# SCH_USBHub_2025-11-01.net
KiCad netlist of a schematic drawn in EasyEDA
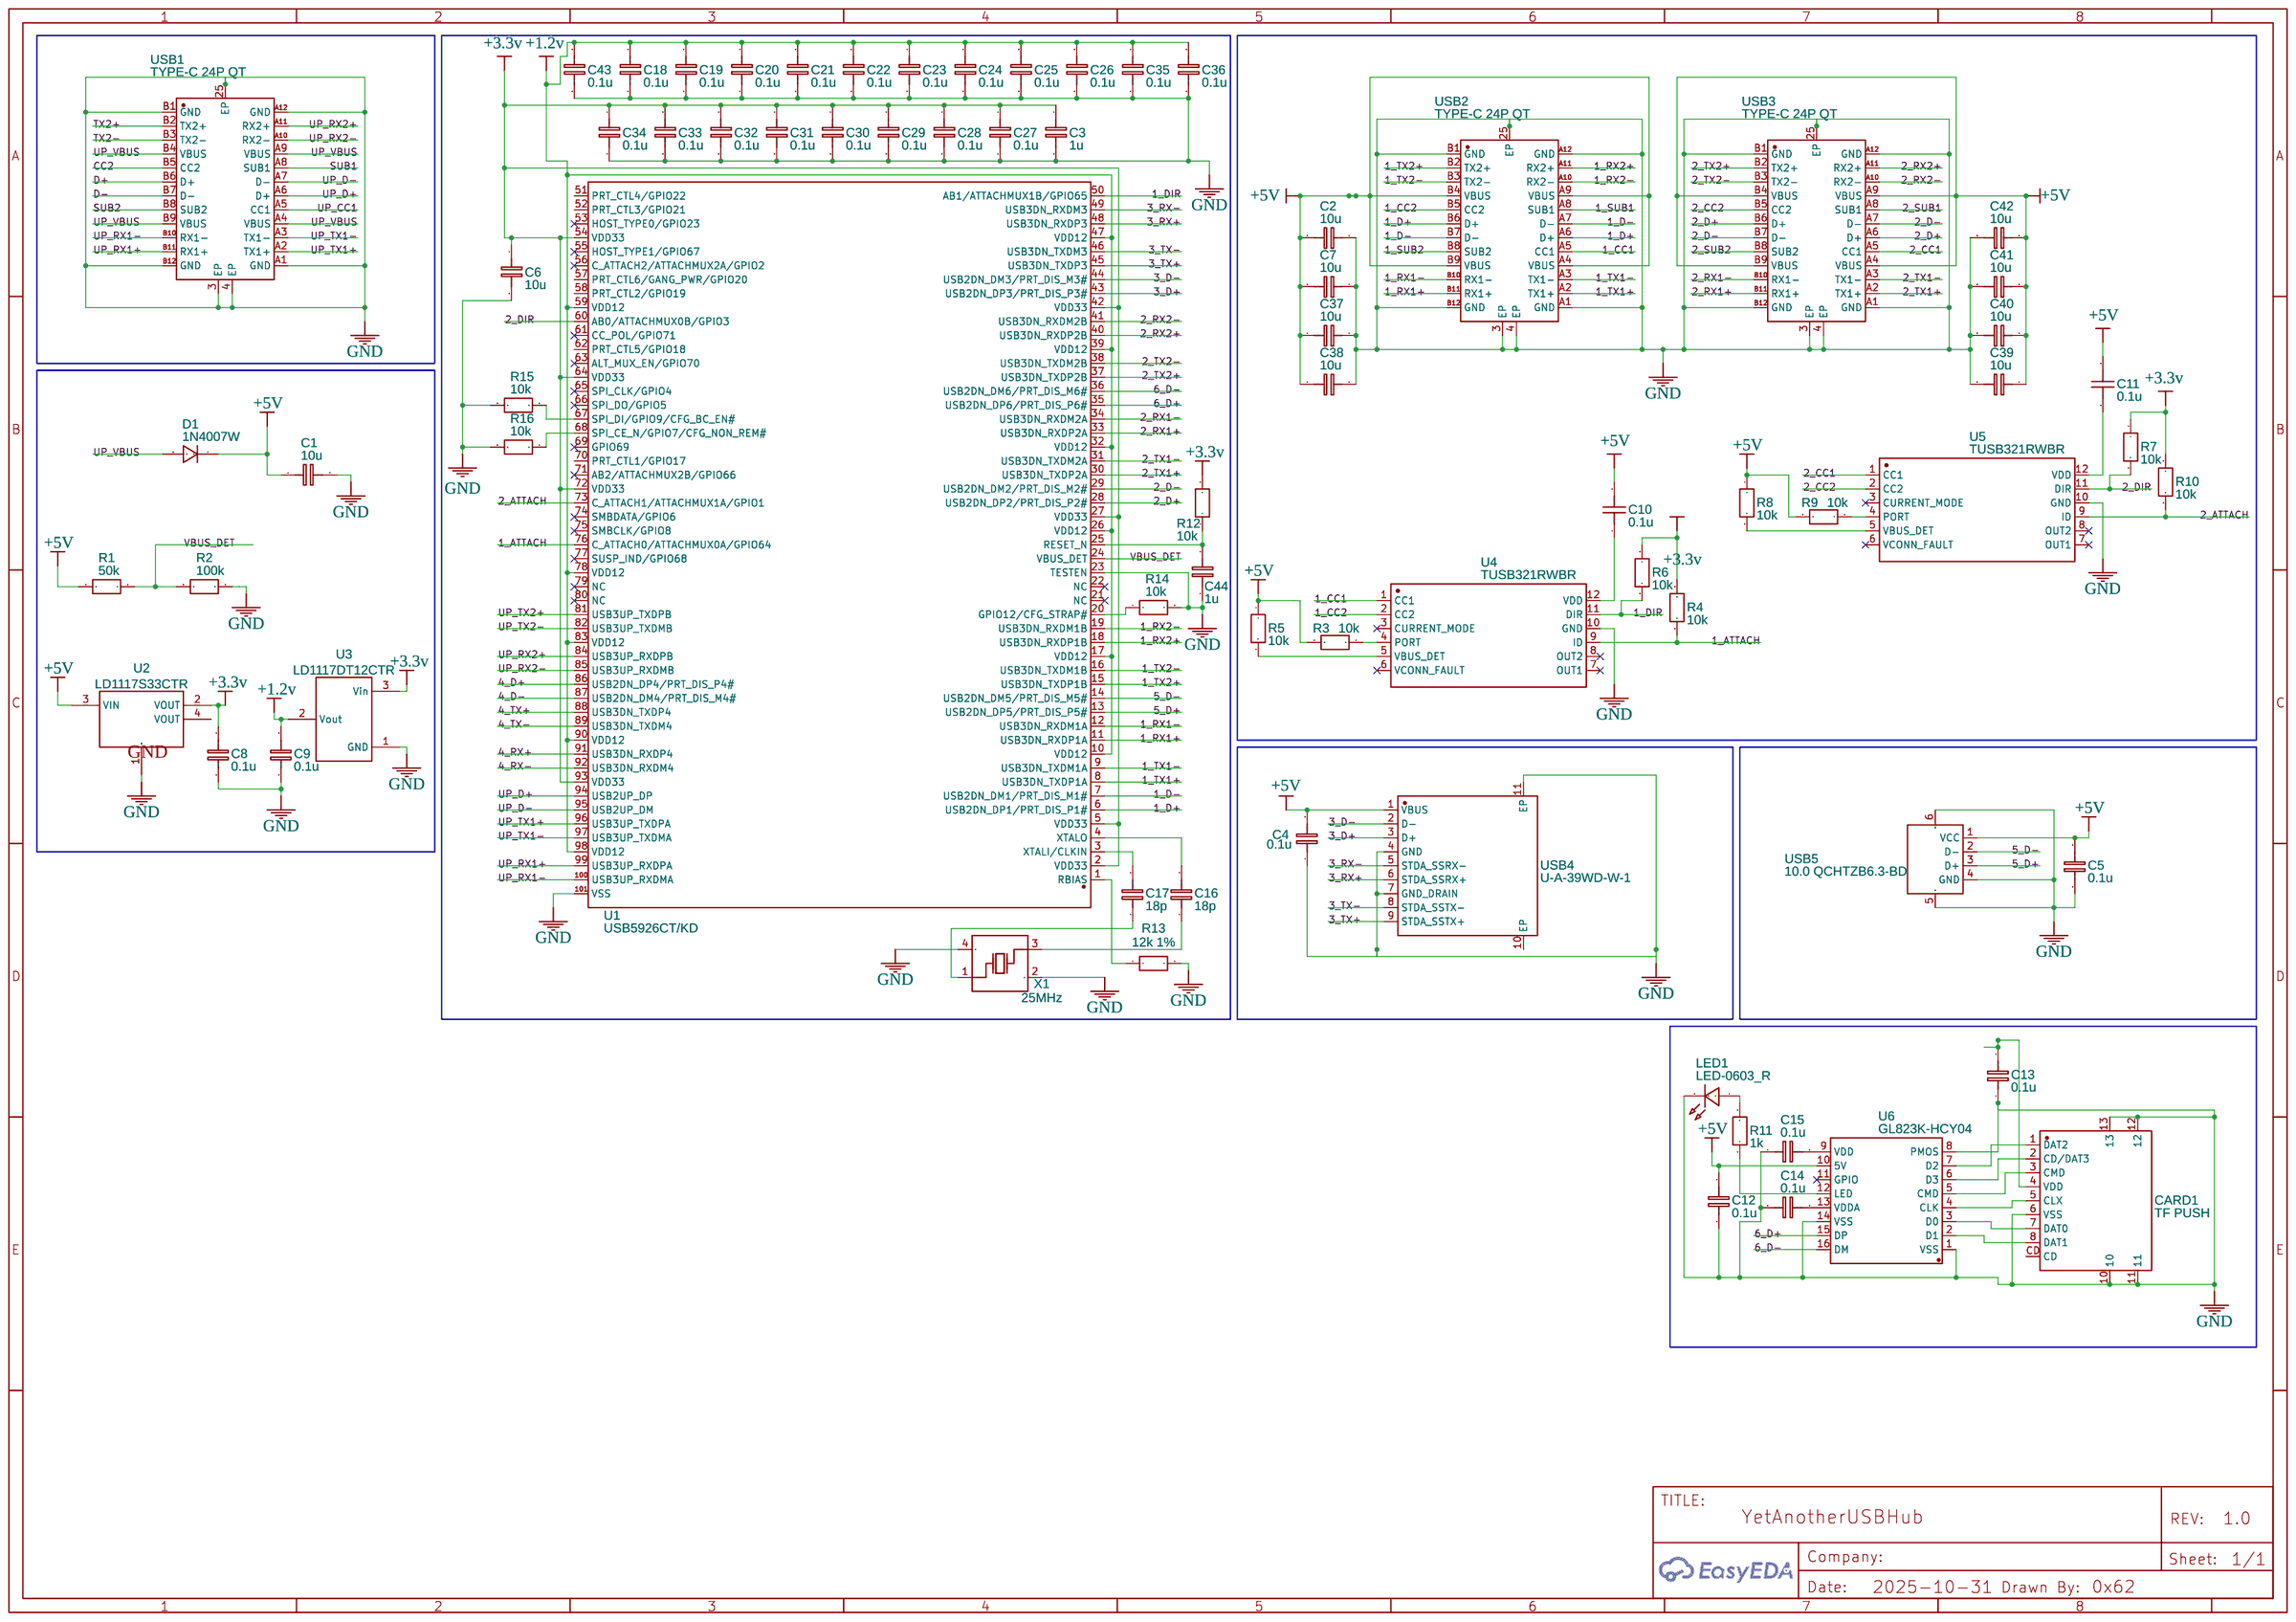
[diagram p0: schematic sheet]

(export (version "E")
  (design (tool "Eeschema 10.0.6"))
  (components
    (comp (ref "C1") (value "10u") (libsource (lib "") (part "C_0603_EU_1")))
    (comp (ref "C2") (value "10u") (libsource (lib "") (part "C_0603_EU_2")))
    (comp (ref "C3") (value "1u") (libsource (lib "") (part "C_0603_EU_7")))
    (comp (ref "C4") (value "0.1u") (libsource (lib "") (part "C_0603_EU")))
    (comp (ref "C5") (value "0.1u") (libsource (lib "") (part "C_0603_EU")))
    (comp (ref "C6") (value "10u") (libsource (lib "") (part "C_0603_EU_6")))
    (comp (ref "C7") (value "10u") (libsource (lib "") (part "C_0603_EU_2")))
    (comp (ref "C8") (value "0.1u") (libsource (lib "") (part "C_0603_EU_4")))
    (comp (ref "C9") (value "0.1u") (libsource (lib "") (part "C_0603_EU_4")))
    (comp (ref "C10") (value "0.1u") (libsource (lib "") (part "C_0603_US_1")))
    (comp (ref "C11") (value "0.1u") (libsource (lib "") (part "C_0603_US")))
    (comp (ref "C12") (value "0.1u") (libsource (lib "") (part "C_0603_EU_3")))
    (comp (ref "C13") (value "0.1u") (libsource (lib "") (part "C_0603_EU_3")))
    (comp (ref "C14") (value "0.1u") (libsource (lib "") (part "C_0603_EU_5")))
    (comp (ref "C15") (value "0.1u") (libsource (lib "") (part "C_0603_EU_5")))
    (comp (ref "C16") (value "18p") (libsource (lib "") (part "C_0603_EU")))
    (comp (ref "C17") (value "18p") (libsource (lib "") (part "C_0603_EU")))
    (comp (ref "C18") (value "0.1u") (libsource (lib "") (part "C_0603_EU_6")))
    (comp (ref "C19") (value "0.1u") (libsource (lib "") (part "C_0603_EU_6")))
    (comp (ref "C20") (value "0.1u") (libsource (lib "") (part "C_0603_EU_7")))
    (comp (ref "C21") (value "0.1u") (libsource (lib "") (part "C_0603_EU_7")))
    (comp (ref "C22") (value "0.1u") (libsource (lib "") (part "C_0603_EU_7")))
    (comp (ref "C23") (value "0.1u") (libsource (lib "") (part "C_0603_EU_7")))
    (comp (ref "C24") (value "0.1u") (libsource (lib "") (part "C_0603_EU_7")))
    (comp (ref "C25") (value "0.1u") (libsource (lib "") (part "C_0603_EU_7")))
    (comp (ref "C26") (value "0.1u") (libsource (lib "") (part "C_0603_EU_7")))
    (comp (ref "C27") (value "0.1u") (libsource (lib "") (part "C_0603_EU_7")))
    (comp (ref "C28") (value "0.1u") (libsource (lib "") (part "C_0603_EU_7")))
    (comp (ref "C29") (value "0.1u") (libsource (lib "") (part "C_0603_EU_7")))
    (comp (ref "C30") (value "0.1u") (libsource (lib "") (part "C_0603_EU_7")))
    (comp (ref "C31") (value "0.1u") (libsource (lib "") (part "C_0603_EU_7")))
    (comp (ref "C32") (value "0.1u") (libsource (lib "") (part "C_0603_EU_6")))
    (comp (ref "C33") (value "0.1u") (libsource (lib "") (part "C_0603_EU_6")))
    (comp (ref "C34") (value "0.1u") (libsource (lib "") (part "C_0603_EU_6")))
    (comp (ref "C35") (value "0.1u") (libsource (lib "") (part "C_0603_EU_7")))
    (comp (ref "C36") (value "0.1u") (libsource (lib "") (part "C_0603_EU_7")))
    (comp (ref "C37") (value "10u") (libsource (lib "") (part "C_0603_EU_2")))
    (comp (ref "C38") (value "10u") (libsource (lib "") (part "C_0603_EU_2")))
    (comp (ref "C39") (value "10u") (libsource (lib "") (part "C_0603_EU_2")))
    (comp (ref "C40") (value "10u") (libsource (lib "") (part "C_0603_EU_2")))
    (comp (ref "C41") (value "10u") (libsource (lib "") (part "C_0603_EU_2")))
    (comp (ref "C42") (value "10u") (libsource (lib "") (part "C_0603_EU_2")))
    (comp (ref "C43") (value "0.1u") (libsource (lib "") (part "C_0603_EU_6")))
    (comp (ref "C44") (value "1u") (libsource (lib "") (part "C_0603_EU_7")))
    (comp (ref "CARD1")
      (value "TF PUSH")
      (fields (field (name "Manufacturer") "SHOU HAN(首韩)"))
      (libsource (lib "") (part "TF PUSH"))
    )
    (comp (ref "D1")
      (value "1N4007W")
      (fields (field (name "Manufacturer") "BLUE ROCKET"))
      (libsource (lib "") (part "1N4007W"))
    )
    (comp (ref "LED1")
      (value "LED-0603_R")
      (fields
        (field (name "Manufacturer Part") "19-217/R6C-AL1M2VY/3T")
        (field (name "Manufacturer") "EVERLIGHT(台湾亿光)")
      )
      (libsource (lib "") (part "LED-0603_R"))
    )
    (comp (ref "R1") (value "50k") (libsource (lib "") (part "R_0603_EU_2")))
    (comp (ref "R2") (value "100k") (libsource (lib "") (part "R_0603_EU_2")))
    (comp (ref "R3") (value "10k") (libsource (lib "") (part "R_0603_EU_3")))
    (comp (ref "R4") (value "10k") (libsource (lib "") (part "R_0603_EU_1")))
    (comp (ref "R5") (value "10k") (libsource (lib "") (part "R_0603_EU")))
    (comp (ref "R6") (value "10k") (libsource (lib "") (part "R_0603_EU")))
    (comp (ref "R7") (value "10k") (libsource (lib "") (part "R_0603_EU")))
    (comp (ref "R8") (value "10k") (libsource (lib "") (part "R_0603_EU")))
    (comp (ref "R9") (value "10k") (libsource (lib "") (part "R_0603_EU_3")))
    (comp (ref "R10") (value "10k") (libsource (lib "") (part "R_0603_EU_1")))
    (comp (ref "R11") (value "1k") (libsource (lib "") (part "R_0603_EU_1")))
    (comp (ref "R12") (value "10k") (libsource (lib "") (part "R_0603_EU_1")))
    (comp (ref "R13") (value "12k 1%") (libsource (lib "") (part "R_0603_EU_2")))
    (comp (ref "R14") (value "10k") (libsource (lib "") (part "R_0603_EU_2")))
    (comp (ref "R15") (value "10k") (libsource (lib "") (part "R_0603_EU_3")))
    (comp (ref "R16") (value "10k") (libsource (lib "") (part "R_0603_EU_3")))
    (comp (ref "U1")
      (value "USB5926CT/KD")
      (fields (field (name "Manufacturer") "MICROCHIP(美国微芯)"))
      (libsource (lib "") (part "USB5926CT/KD"))
    )
    (comp (ref "U2")
      (value "LD1117S33CTR")
      (fields (field (name "Manufacturer") "ST(意法半导体)"))
      (libsource (lib "") (part "LD1117S33CTR"))
    )
    (comp (ref "U3")
      (value "LD1117DT12CTR")
      (fields (field (name "Manufacturer") "ST(意法半导体)"))
      (libsource (lib "") (part "LD1117DT12CTR"))
    )
    (comp (ref "U4")
      (value "TUSB321RWBR")
      (fields (field (name "Manufacturer") "TI(德州仪器)"))
      (libsource (lib "") (part "TUSB321RWBR"))
    )
    (comp (ref "U5")
      (value "TUSB321RWBR")
      (fields (field (name "Manufacturer") "TI(德州仪器)"))
      (libsource (lib "") (part "TUSB321RWBR"))
    )
    (comp (ref "U6")
      (value "GL823K-HCY04")
      (fields (field (name "Manufacturer") "GENESYS(创惟)"))
      (libsource (lib "") (part "GL823K-HCY04"))
    )
    (comp (ref "USB1")
      (value "TYPE-C 24P QT")
      (fields (field (name "Manufacturer") "SHOU HAN(首韩)"))
      (libsource (lib "") (part "TYPE-C 24P QT"))
    )
    (comp (ref "USB2")
      (value "TYPE-C 24P QT")
      (fields (field (name "Manufacturer") "SHOU HAN(首韩)"))
      (libsource (lib "") (part "TYPE-C 24P QT"))
    )
    (comp (ref "USB3")
      (value "TYPE-C 24P QT")
      (fields (field (name "Manufacturer") "SHOU HAN(首韩)"))
      (libsource (lib "") (part "TYPE-C 24P QT"))
    )
    (comp (ref "USB4")
      (value "U-A-39WD-W-1")
      (fields (field (name "Manufacturer") "韩国韩荣"))
      (libsource (lib "") (part "U-A-39WD-W-1"))
    )
    (comp (ref "USB5")
      (value "10.0 QCHTZB6.3-BD")
      (fields (field (name "Manufacturer") "SHOU HAN(首韩)"))
      (libsource (lib "") (part "10.0 QCHTZB6.3-BD"))
    )
    (comp (ref "X1")
      (value "25MHz")
      (fields (field (name "Manufacturer Part") "X322525MOB4SI") (field (name "Manufacturer") "YXC(扬兴晶振)"))
      (libsource (lib "") (part "X322525MOB4SI"))
    )
  )
  (nets
    (net (code "1") (name "+1.2v") (class "Default")
      (node (ref "C18") (pin "1") (pinfunction "1_1") (pintype "unspecified"))
      (node (ref "C19") (pin "1") (pinfunction "1_1") (pintype "unspecified"))
      (node (ref "C20") (pin "1") (pinfunction "1_1") (pintype "unspecified"))
      (node (ref "C21") (pin "1") (pinfunction "1_1") (pintype "unspecified"))
      (node (ref "C22") (pin "1") (pinfunction "1_1") (pintype "unspecified"))
      (node (ref "C23") (pin "1") (pinfunction "1_1") (pintype "unspecified"))
      (node (ref "C24") (pin "1") (pinfunction "1_1") (pintype "unspecified"))
      (node (ref "C25") (pin "1") (pinfunction "1_1") (pintype "unspecified"))
      (node (ref "C26") (pin "1") (pinfunction "1_1") (pintype "unspecified"))
      (node (ref "C35") (pin "1") (pinfunction "1_1") (pintype "unspecified"))
      (node (ref "C36") (pin "1") (pinfunction "1_1") (pintype "unspecified"))
      (node (ref "C43") (pin "1") (pinfunction "1_1") (pintype "unspecified"))
      (node (ref "C9") (pin "2") (pinfunction "2_2") (pintype "unspecified"))
      (node (ref "U1") (pin "10") (pinfunction "VDD12_10") (pintype "unspecified"))
      (node (ref "U1") (pin "17") (pinfunction "VDD12_17") (pintype "unspecified"))
      (node (ref "U1") (pin "26") (pinfunction "VDD12_26") (pintype "unspecified"))
      (node (ref "U1") (pin "32") (pinfunction "VDD12_32") (pintype "unspecified"))
      (node (ref "U1") (pin "39") (pinfunction "VDD12_39") (pintype "unspecified"))
      (node (ref "U1") (pin "47") (pinfunction "VDD12_47") (pintype "unspecified"))
      (node (ref "U1") (pin "59") (pinfunction "VDD12_59") (pintype "unspecified"))
      (node (ref "U1") (pin "78") (pinfunction "VDD12_78") (pintype "unspecified"))
      (node (ref "U1") (pin "83") (pinfunction "VDD12_83") (pintype "unspecified"))
      (node (ref "U1") (pin "90") (pinfunction "VDD12_90") (pintype "unspecified"))
      (node (ref "U1") (pin "98") (pinfunction "VDD12_98") (pintype "unspecified"))
      (node (ref "U3") (pin "2") (pinfunction "Vout_2") (pintype "unspecified"))
    )
    (net (code "2") (name "+3.3v") (class "Default")
      (node (ref "C27") (pin "1") (pinfunction "1_1") (pintype "unspecified"))
      (node (ref "C28") (pin "1") (pinfunction "1_1") (pintype "unspecified"))
      (node (ref "C29") (pin "1") (pinfunction "1_1") (pintype "unspecified"))
      (node (ref "C3") (pin "1") (pinfunction "1_1") (pintype "unspecified"))
      (node (ref "C30") (pin "1") (pinfunction "1_1") (pintype "unspecified"))
      (node (ref "C31") (pin "1") (pinfunction "1_1") (pintype "unspecified"))
      (node (ref "C32") (pin "1") (pinfunction "1_1") (pintype "unspecified"))
      (node (ref "C33") (pin "1") (pinfunction "1_1") (pintype "unspecified"))
      (node (ref "C34") (pin "1") (pinfunction "1_1") (pintype "unspecified"))
      (node (ref "C6") (pin "1") (pinfunction "1_1") (pintype "unspecified"))
      (node (ref "C8") (pin "2") (pinfunction "2_2") (pintype "unspecified"))
      (node (ref "R10") (pin "2") (pinfunction "2_2") (pintype "unspecified"))
      (node (ref "R12") (pin "2") (pinfunction "2_2") (pintype "unspecified"))
      (node (ref "R4") (pin "2") (pinfunction "2_2") (pintype "unspecified"))
      (node (ref "R6") (pin "1") (pinfunction "1_1") (pintype "unspecified"))
      (node (ref "R7") (pin "1") (pinfunction "1_1") (pintype "unspecified"))
      (node (ref "U1") (pin "2") (pinfunction "VDD33_2") (pintype "unspecified"))
      (node (ref "U1") (pin "27") (pinfunction "VDD33_27") (pintype "unspecified"))
      (node (ref "U1") (pin "42") (pinfunction "VDD33_42") (pintype "unspecified"))
      (node (ref "U1") (pin "5") (pinfunction "VDD33_5") (pintype "unspecified"))
      (node (ref "U1") (pin "54") (pinfunction "VDD33_54") (pintype "unspecified"))
      (node (ref "U1") (pin "64") (pinfunction "VDD33_64") (pintype "unspecified"))
      (node (ref "U1") (pin "72") (pinfunction "VDD33_72") (pintype "unspecified"))
      (node (ref "U1") (pin "93") (pinfunction "VDD33_93") (pintype "unspecified"))
      (node (ref "U2") (pin "2") (pinfunction "VOUT_2") (pintype "passive"))
      (node (ref "U3") (pin "3") (pinfunction "Vin_3") (pintype "unspecified"))
    )
    (net (code "3") (name "+5V") (class "Default")
      (node (ref "C1") (pin "1") (pinfunction "1_1") (pintype "unspecified"))
      (node (ref "C10") (pin "2") (pinfunction "2_2") (pintype "unspecified"))
      (node (ref "C11") (pin "1") (pinfunction "1_1") (pintype "unspecified"))
      (node (ref "C12") (pin "2") (pinfunction "2_2") (pintype "unspecified"))
      (node (ref "C2") (pin "2") (pinfunction "2_2") (pintype "unspecified"))
      (node (ref "C37") (pin "2") (pinfunction "2_2") (pintype "unspecified"))
      (node (ref "C38") (pin "2") (pinfunction "2_2") (pintype "unspecified"))
      (node (ref "C39") (pin "1") (pinfunction "1_1") (pintype "unspecified"))
      (node (ref "C4") (pin "2") (pinfunction "2_2") (pintype "unspecified"))
      (node (ref "C40") (pin "1") (pinfunction "1_1") (pintype "unspecified"))
      (node (ref "C41") (pin "1") (pinfunction "1_1") (pintype "unspecified"))
      (node (ref "C42") (pin "1") (pinfunction "1_1") (pintype "unspecified"))
      (node (ref "C5") (pin "2") (pinfunction "2_2") (pintype "unspecified"))
      (node (ref "C7") (pin "2") (pinfunction "2_2") (pintype "unspecified"))
      (node (ref "D1") (pin "1") (pinfunction "1_1") (pintype "unspecified"))
      (node (ref "R1") (pin "1") (pinfunction "1_1") (pintype "unspecified"))
      (node (ref "R3") (pin "2") (pinfunction "2_2") (pintype "unspecified"))
      (node (ref "R5") (pin "1") (pinfunction "1_1") (pintype "unspecified"))
      (node (ref "R8") (pin "1") (pinfunction "1_1") (pintype "unspecified"))
      (node (ref "R9") (pin "2") (pinfunction "2_2") (pintype "unspecified"))
      (node (ref "U2") (pin "3") (pinfunction "VIN_3") (pintype "passive"))
      (node (ref "U6") (pin "10") (pinfunction "5V_10") (pintype "unspecified"))
      (node (ref "USB2") (pin "A4") (pinfunction "VBUS_A4") (pintype "unspecified"))
      (node (ref "USB2") (pin "A9") (pinfunction "VBUS_A9") (pintype "unspecified"))
      (node (ref "USB2") (pin "B4") (pinfunction "VBUS_B4") (pintype "unspecified"))
      (node (ref "USB2") (pin "B9") (pinfunction "VBUS_B9") (pintype "unspecified"))
      (node (ref "USB3") (pin "A4") (pinfunction "VBUS_A4") (pintype "unspecified"))
      (node (ref "USB3") (pin "A9") (pinfunction "VBUS_A9") (pintype "unspecified"))
      (node (ref "USB3") (pin "B4") (pinfunction "VBUS_B4") (pintype "unspecified"))
      (node (ref "USB3") (pin "B9") (pinfunction "VBUS_B9") (pintype "unspecified"))
      (node (ref "USB4") (pin "1") (pinfunction "VBUS_1") (pintype "unspecified"))
      (node (ref "USB5") (pin "1") (pinfunction "VCC_1") (pintype "input"))
    )
    (net (code "4") (name "/1_ATTACH") (class "Default")
      (node (ref "R4") (pin "1") (pinfunction "1_1") (pintype "unspecified"))
      (node (ref "U1") (pin "76") (pinfunction "C_ATTACH0/ATTACHMUX0A/GPIO64_76") (pintype "unspecified"))
      (node (ref "U4") (pin "9") (pinfunction "ID_9") (pintype "unspecified"))
    )
    (net (code "5") (name "/1_CC1") (class "Default")
      (node (ref "U4") (pin "1") (pinfunction "CC1_1") (pintype "unspecified"))
      (node (ref "USB2") (pin "A5") (pinfunction "CC1_A5") (pintype "unspecified"))
    )
    (net (code "6") (name "/1_CC2") (class "Default")
      (node (ref "U4") (pin "2") (pinfunction "CC2_2") (pintype "unspecified"))
      (node (ref "USB2") (pin "B5") (pinfunction "CC2_B5") (pintype "unspecified"))
    )
    (net (code "7") (name "/1_D+") (class "Default")
      (node (ref "U1") (pin "6") (pinfunction "USB2DN_DP1/PRT_DIS_P1#_6") (pintype "unspecified"))
      (node (ref "USB2") (pin "A6") (pinfunction "D+_A6") (pintype "unspecified"))
      (node (ref "USB2") (pin "B6") (pinfunction "D+_B6") (pintype "unspecified"))
    )
    (net (code "8") (name "/1_D-") (class "Default")
      (node (ref "U1") (pin "7") (pinfunction "USB2DN_DM1/PRT_DIS_M1#_7") (pintype "unspecified"))
      (node (ref "USB2") (pin "A7") (pinfunction "D-_A7") (pintype "unspecified"))
      (node (ref "USB2") (pin "B7") (pinfunction "D-_B7") (pintype "unspecified"))
    )
    (net (code "9") (name "/1_DIR") (class "Default")
      (node (ref "R6") (pin "2") (pinfunction "2_2") (pintype "unspecified"))
      (node (ref "U1") (pin "50") (pinfunction "AB1/ATTACHMUX1B/GPIO65_50") (pintype "unspecified"))
      (node (ref "U4") (pin "11") (pinfunction "DIR_11") (pintype "unspecified"))
    )
    (net (code "10") (name "/1_RX1+") (class "Default")
      (node (ref "U1") (pin "11") (pinfunction "USB3DN_RXDP1A_11") (pintype "unspecified"))
      (node (ref "USB2") (pin "B11") (pinfunction "RX1+_B11") (pintype "unspecified"))
    )
    (net (code "11") (name "/1_RX1-") (class "Default")
      (node (ref "U1") (pin "12") (pinfunction "USB3DN_RXDM1A_12") (pintype "unspecified"))
      (node (ref "USB2") (pin "B10") (pinfunction "RX1-_B10") (pintype "unspecified"))
    )
    (net (code "12") (name "/1_RX2+") (class "Default")
      (node (ref "U1") (pin "18") (pinfunction "USB3DN_RXDP1B_18") (pintype "unspecified"))
      (node (ref "USB2") (pin "A11") (pinfunction "RX2+_A11") (pintype "unspecified"))
    )
    (net (code "13") (name "/1_RX2-") (class "Default")
      (node (ref "U1") (pin "19") (pinfunction "USB3DN_RXDM1B_19") (pintype "unspecified"))
      (node (ref "USB2") (pin "A10") (pinfunction "RX2-_A10") (pintype "unspecified"))
    )
    (net (code "14") (name "/1_SUB1") (class "Default")
      (node (ref "USB2") (pin "A8") (pinfunction "SUB1_A8") (pintype "unspecified"))
    )
    (net (code "15") (name "/1_SUB2") (class "Default")
      (node (ref "USB2") (pin "B8") (pinfunction "SUB2_B8") (pintype "unspecified"))
    )
    (net (code "16") (name "/1_TX1+") (class "Default")
      (node (ref "U1") (pin "8") (pinfunction "USB3DN_TXDP1A_8") (pintype "unspecified"))
      (node (ref "USB2") (pin "A2") (pinfunction "TX1+_A2") (pintype "unspecified"))
    )
    (net (code "17") (name "/1_TX1-") (class "Default")
      (node (ref "U1") (pin "9") (pinfunction "USB3DN_TXDM1A_9") (pintype "unspecified"))
      (node (ref "USB2") (pin "A3") (pinfunction "TX1-_A3") (pintype "unspecified"))
    )
    (net (code "18") (name "/1_TX2+") (class "Default")
      (node (ref "U1") (pin "15") (pinfunction "USB3DN_TXDP1B_15") (pintype "unspecified"))
      (node (ref "USB2") (pin "B2") (pinfunction "TX2+_B2") (pintype "unspecified"))
    )
    (net (code "19") (name "/1_TX2-") (class "Default")
      (node (ref "U1") (pin "16") (pinfunction "USB3DN_TXDM1B_16") (pintype "unspecified"))
      (node (ref "USB2") (pin "B3") (pinfunction "TX2-_B3") (pintype "unspecified"))
    )
    (net (code "20") (name "/2_ATTACH") (class "Default")
      (node (ref "R10") (pin "1") (pinfunction "1_1") (pintype "unspecified"))
      (node (ref "U1") (pin "73") (pinfunction "C_ATTACH1/ATTACHMUX1A/GPIO1_73") (pintype "unspecified"))
      (node (ref "U5") (pin "9") (pinfunction "ID_9") (pintype "unspecified"))
    )
    (net (code "21") (name "/2_CC1") (class "Default")
      (node (ref "U5") (pin "1") (pinfunction "CC1_1") (pintype "unspecified"))
      (node (ref "USB3") (pin "A5") (pinfunction "CC1_A5") (pintype "unspecified"))
    )
    (net (code "22") (name "/2_CC2") (class "Default")
      (node (ref "U5") (pin "2") (pinfunction "CC2_2") (pintype "unspecified"))
      (node (ref "USB3") (pin "B5") (pinfunction "CC2_B5") (pintype "unspecified"))
    )
    (net (code "23") (name "/2_D+") (class "Default")
      (node (ref "U1") (pin "28") (pinfunction "USB2DN_DP2/PRT_DIS_P2#_28") (pintype "unspecified"))
      (node (ref "USB3") (pin "A6") (pinfunction "D+_A6") (pintype "unspecified"))
      (node (ref "USB3") (pin "B6") (pinfunction "D+_B6") (pintype "unspecified"))
    )
    (net (code "24") (name "/2_D-") (class "Default")
      (node (ref "U1") (pin "29") (pinfunction "USB2DN_DM2/PRT_DIS_M2#_29") (pintype "unspecified"))
      (node (ref "USB3") (pin "A7") (pinfunction "D-_A7") (pintype "unspecified"))
      (node (ref "USB3") (pin "B7") (pinfunction "D-_B7") (pintype "unspecified"))
    )
    (net (code "25") (name "/2_DIR") (class "Default")
      (node (ref "R7") (pin "2") (pinfunction "2_2") (pintype "unspecified"))
      (node (ref "U1") (pin "60") (pinfunction "AB0/ATTACHMUX0B/GPIO3_60") (pintype "unspecified"))
      (node (ref "U5") (pin "11") (pinfunction "DIR_11") (pintype "unspecified"))
    )
    (net (code "26") (name "/2_RX1+") (class "Default")
      (node (ref "U1") (pin "33") (pinfunction "USB3DN_RXDP2A_33") (pintype "unspecified"))
      (node (ref "USB3") (pin "B11") (pinfunction "RX1+_B11") (pintype "unspecified"))
    )
    (net (code "27") (name "/2_RX1-") (class "Default")
      (node (ref "U1") (pin "34") (pinfunction "USB3DN_RXDM2A_34") (pintype "unspecified"))
      (node (ref "USB3") (pin "B10") (pinfunction "RX1-_B10") (pintype "unspecified"))
    )
    (net (code "28") (name "/2_RX2+") (class "Default")
      (node (ref "U1") (pin "40") (pinfunction "USB3DN_RXDP2B_40") (pintype "unspecified"))
      (node (ref "USB3") (pin "A11") (pinfunction "RX2+_A11") (pintype "unspecified"))
    )
    (net (code "29") (name "/2_RX2-") (class "Default")
      (node (ref "U1") (pin "41") (pinfunction "USB3DN_RXDM2B_41") (pintype "unspecified"))
      (node (ref "USB3") (pin "A10") (pinfunction "RX2-_A10") (pintype "unspecified"))
    )
    (net (code "30") (name "/2_SUB1") (class "Default")
      (node (ref "USB3") (pin "A8") (pinfunction "SUB1_A8") (pintype "unspecified"))
    )
    (net (code "31") (name "/2_SUB2") (class "Default")
      (node (ref "USB3") (pin "B8") (pinfunction "SUB2_B8") (pintype "unspecified"))
    )
    (net (code "32") (name "/2_TX1+") (class "Default")
      (node (ref "U1") (pin "30") (pinfunction "USB3DN_TXDP2A_30") (pintype "unspecified"))
      (node (ref "USB3") (pin "A2") (pinfunction "TX1+_A2") (pintype "unspecified"))
    )
    (net (code "33") (name "/2_TX1-") (class "Default")
      (node (ref "U1") (pin "31") (pinfunction "USB3DN_TXDM2A_31") (pintype "unspecified"))
      (node (ref "USB3") (pin "A3") (pinfunction "TX1-_A3") (pintype "unspecified"))
    )
    (net (code "34") (name "/2_TX2+") (class "Default")
      (node (ref "U1") (pin "37") (pinfunction "USB3DN_TXDP2B_37") (pintype "unspecified"))
      (node (ref "USB3") (pin "B2") (pinfunction "TX2+_B2") (pintype "unspecified"))
    )
    (net (code "35") (name "/2_TX2-") (class "Default")
      (node (ref "U1") (pin "38") (pinfunction "USB3DN_TXDM2B_38") (pintype "unspecified"))
      (node (ref "USB3") (pin "B3") (pinfunction "TX2-_B3") (pintype "unspecified"))
    )
    (net (code "36") (name "/3_D+") (class "Default")
      (node (ref "U1") (pin "43") (pinfunction "USB2DN_DP3/PRT_DIS_P3#_43") (pintype "unspecified"))
      (node (ref "USB4") (pin "3") (pinfunction "D+_3") (pintype "unspecified"))
    )
    (net (code "37") (name "/3_D-") (class "Default")
      (node (ref "U1") (pin "44") (pinfunction "USB2DN_DM3/PRT_DIS_M3#_44") (pintype "unspecified"))
      (node (ref "USB4") (pin "2") (pinfunction "D-_2") (pintype "unspecified"))
    )
    (net (code "38") (name "/3_RX+") (class "Default")
      (node (ref "U1") (pin "48") (pinfunction "USB3DN_RXDP3_48") (pintype "unspecified"))
      (node (ref "USB4") (pin "6") (pinfunction "STDA_SSRX+_6") (pintype "unspecified"))
    )
    (net (code "39") (name "/3_RX-") (class "Default")
      (node (ref "U1") (pin "49") (pinfunction "USB3DN_RXDM3_49") (pintype "unspecified"))
      (node (ref "USB4") (pin "5") (pinfunction "STDA_SSRX-_5") (pintype "unspecified"))
    )
    (net (code "40") (name "/3_TX+") (class "Default")
      (node (ref "U1") (pin "45") (pinfunction "USB3DN_TXDP3_45") (pintype "unspecified"))
      (node (ref "USB4") (pin "9") (pinfunction "STDA_SSTX+_9") (pintype "unspecified"))
    )
    (net (code "41") (name "/3_TX-") (class "Default")
      (node (ref "U1") (pin "46") (pinfunction "USB3DN_TXDM3_46") (pintype "unspecified"))
      (node (ref "USB4") (pin "8") (pinfunction "STDA_SSTX-_8") (pintype "unspecified"))
    )
    (net (code "42") (name "/4_D+") (class "Default")
      (node (ref "U1") (pin "86") (pinfunction "USB2DN_DP4/PRT_DIS_P4#_86") (pintype "unspecified"))
    )
    (net (code "43") (name "/4_D-") (class "Default")
      (node (ref "U1") (pin "87") (pinfunction "USB2DN_DM4/PRT_DIS_M4#_87") (pintype "unspecified"))
    )
    (net (code "44") (name "/4_RX+") (class "Default")
      (node (ref "U1") (pin "91") (pinfunction "USB3DN_RXDP4_91") (pintype "unspecified"))
    )
    (net (code "45") (name "/4_RX-") (class "Default")
      (node (ref "U1") (pin "92") (pinfunction "USB3DN_RXDM4_92") (pintype "unspecified"))
    )
    (net (code "46") (name "/4_TX+") (class "Default")
      (node (ref "U1") (pin "88") (pinfunction "USB3DN_TXDP4_88") (pintype "unspecified"))
    )
    (net (code "47") (name "/4_TX-") (class "Default")
      (node (ref "U1") (pin "89") (pinfunction "USB3DN_TXDM4_89") (pintype "unspecified"))
    )
    (net (code "48") (name "/5_D+") (class "Default")
      (node (ref "U1") (pin "13") (pinfunction "USB2DN_DP5/PRT_DIS_P5#_13") (pintype "unspecified"))
      (node (ref "USB5") (pin "3") (pinfunction "D+_3") (pintype "input"))
    )
    (net (code "49") (name "/5_D-") (class "Default")
      (node (ref "U1") (pin "14") (pinfunction "USB2DN_DM5/PRT_DIS_M5#_14") (pintype "unspecified"))
      (node (ref "USB5") (pin "2") (pinfunction "D-_2") (pintype "input"))
    )
    (net (code "50") (name "/6_D+") (class "Default")
      (node (ref "U1") (pin "35") (pinfunction "USB2DN_DP6/PRT_DIS_P6#_35") (pintype "unspecified"))
      (node (ref "U6") (pin "15") (pinfunction "DP_15") (pintype "unspecified"))
    )
    (net (code "51") (name "/6_D-") (class "Default")
      (node (ref "U1") (pin "36") (pinfunction "USB2DN_DM6/PRT_DIS_M6#_36") (pintype "unspecified"))
      (node (ref "U6") (pin "16") (pinfunction "DM_16") (pintype "unspecified"))
    )
    (net (code "52") (name "/CC2") (class "Default")
      (node (ref "USB1") (pin "B5") (pinfunction "CC2_B5") (pintype "unspecified"))
    )
    (net (code "53") (name "/D+") (class "Default")
      (node (ref "USB1") (pin "B6") (pinfunction "D+_B6") (pintype "unspecified"))
    )
    (net (code "54") (name "/D-") (class "Default")
      (node (ref "USB1") (pin "B7") (pinfunction "D-_B7") (pintype "unspecified"))
    )
    (net (code "55") (name "/SUB1") (class "Default")
      (node (ref "USB1") (pin "A8") (pinfunction "SUB1_A8") (pintype "unspecified"))
    )
    (net (code "56") (name "/SUB2") (class "Default")
      (node (ref "USB1") (pin "B8") (pinfunction "SUB2_B8") (pintype "unspecified"))
    )
    (net (code "57") (name "/TX2+") (class "Default")
      (node (ref "USB1") (pin "B2") (pinfunction "TX2+_B2") (pintype "unspecified"))
    )
    (net (code "58") (name "/TX2-") (class "Default")
      (node (ref "USB1") (pin "B3") (pinfunction "TX2-_B3") (pintype "unspecified"))
    )
    (net (code "59") (name "/UP_CC1") (class "Default")
      (node (ref "USB1") (pin "A5") (pinfunction "CC1_A5") (pintype "unspecified"))
    )
    (net (code "60") (name "/UP_D+") (class "Default")
      (node (ref "U1") (pin "94") (pinfunction "USB2UP_DP_94") (pintype "unspecified"))
      (node (ref "USB1") (pin "A6") (pinfunction "D+_A6") (pintype "unspecified"))
    )
    (net (code "61") (name "/UP_D-") (class "Default")
      (node (ref "U1") (pin "95") (pinfunction "USB2UP_DM_95") (pintype "unspecified"))
      (node (ref "USB1") (pin "A7") (pinfunction "D-_A7") (pintype "unspecified"))
    )
    (net (code "62") (name "/UP_RX1+") (class "Default")
      (node (ref "U1") (pin "99") (pinfunction "USB3UP_RXDPA_99") (pintype "unspecified"))
      (node (ref "USB1") (pin "B11") (pinfunction "RX1+_B11") (pintype "unspecified"))
    )
    (net (code "63") (name "/UP_RX1-") (class "Default")
      (node (ref "U1") (pin "100") (pinfunction "USB3UP_RXDMA_100") (pintype "unspecified"))
      (node (ref "USB1") (pin "B10") (pinfunction "RX1-_B10") (pintype "unspecified"))
    )
    (net (code "64") (name "/UP_RX2+") (class "Default")
      (node (ref "U1") (pin "84") (pinfunction "USB3UP_RXDPB_84") (pintype "unspecified"))
      (node (ref "USB1") (pin "A11") (pinfunction "RX2+_A11") (pintype "unspecified"))
    )
    (net (code "65") (name "/UP_RX2-") (class "Default")
      (node (ref "U1") (pin "85") (pinfunction "USB3UP_RXDMB_85") (pintype "unspecified"))
      (node (ref "USB1") (pin "A10") (pinfunction "RX2-_A10") (pintype "unspecified"))
    )
    (net (code "66") (name "/UP_TX1+") (class "Default")
      (node (ref "U1") (pin "96") (pinfunction "USB3UP_TXDPA_96") (pintype "unspecified"))
      (node (ref "USB1") (pin "A2") (pinfunction "TX1+_A2") (pintype "unspecified"))
    )
    (net (code "67") (name "/UP_TX1-") (class "Default")
      (node (ref "U1") (pin "97") (pinfunction "USB3UP_TXDMA_97") (pintype "unspecified"))
      (node (ref "USB1") (pin "A3") (pinfunction "TX1-_A3") (pintype "unspecified"))
    )
    (net (code "68") (name "/UP_TX2+") (class "Default")
      (node (ref "U1") (pin "81") (pinfunction "USB3UP_TXDPB_81") (pintype "unspecified"))
    )
    (net (code "69") (name "/UP_TX2-") (class "Default")
      (node (ref "U1") (pin "82") (pinfunction "USB3UP_TXDMB_82") (pintype "unspecified"))
    )
    (net (code "70") (name "/UP_VBUS") (class "Default")
      (node (ref "D1") (pin "2") (pinfunction "2_2") (pintype "unspecified"))
      (node (ref "USB1") (pin "A4") (pinfunction "VBUS_A4") (pintype "unspecified"))
      (node (ref "USB1") (pin "A9") (pinfunction "VBUS_A9") (pintype "unspecified"))
      (node (ref "USB1") (pin "B4") (pinfunction "VBUS_B4") (pintype "unspecified"))
      (node (ref "USB1") (pin "B9") (pinfunction "VBUS_B9") (pintype "unspecified"))
    )
    (net (code "71") (name "/VBUS_DET") (class "Default")
      (node (ref "R1") (pin "2") (pinfunction "2_2") (pintype "unspecified"))
      (node (ref "R2") (pin "1") (pinfunction "1_1") (pintype "unspecified"))
      (node (ref "U1") (pin "24") (pinfunction "VBUS_DET_24") (pintype "unspecified"))
    )
    (net (code "72") (name "GND") (class "Default")
      (node (ref "C1") (pin "2") (pinfunction "2_2") (pintype "unspecified"))
      (node (ref "C12") (pin "1") (pinfunction "1_1") (pintype "unspecified"))
      (node (ref "C13") (pin "1") (pinfunction "1_1") (pintype "unspecified"))
      (node (ref "C14") (pin "1") (pinfunction "1_1") (pintype "unspecified"))
      (node (ref "C15") (pin "1") (pinfunction "1_1") (pintype "unspecified"))
      (node (ref "C18") (pin "2") (pinfunction "2_2") (pintype "unspecified"))
      (node (ref "C19") (pin "2") (pinfunction "2_2") (pintype "unspecified"))
      (node (ref "C2") (pin "1") (pinfunction "1_1") (pintype "unspecified"))
      (node (ref "C20") (pin "2") (pinfunction "2_2") (pintype "unspecified"))
      (node (ref "C21") (pin "2") (pinfunction "2_2") (pintype "unspecified"))
      (node (ref "C22") (pin "2") (pinfunction "2_2") (pintype "unspecified"))
      (node (ref "C23") (pin "2") (pinfunction "2_2") (pintype "unspecified"))
      (node (ref "C24") (pin "2") (pinfunction "2_2") (pintype "unspecified"))
      (node (ref "C25") (pin "2") (pinfunction "2_2") (pintype "unspecified"))
      (node (ref "C26") (pin "2") (pinfunction "2_2") (pintype "unspecified"))
      (node (ref "C27") (pin "2") (pinfunction "2_2") (pintype "unspecified"))
      (node (ref "C28") (pin "2") (pinfunction "2_2") (pintype "unspecified"))
      (node (ref "C29") (pin "2") (pinfunction "2_2") (pintype "unspecified"))
      (node (ref "C3") (pin "2") (pinfunction "2_2") (pintype "unspecified"))
      (node (ref "C30") (pin "2") (pinfunction "2_2") (pintype "unspecified"))
      (node (ref "C31") (pin "2") (pinfunction "2_2") (pintype "unspecified"))
      (node (ref "C32") (pin "2") (pinfunction "2_2") (pintype "unspecified"))
      (node (ref "C33") (pin "2") (pinfunction "2_2") (pintype "unspecified"))
      (node (ref "C34") (pin "2") (pinfunction "2_2") (pintype "unspecified"))
      (node (ref "C35") (pin "2") (pinfunction "2_2") (pintype "unspecified"))
      (node (ref "C36") (pin "2") (pinfunction "2_2") (pintype "unspecified"))
      (node (ref "C37") (pin "1") (pinfunction "1_1") (pintype "unspecified"))
      (node (ref "C38") (pin "1") (pinfunction "1_1") (pintype "unspecified"))
      (node (ref "C39") (pin "2") (pinfunction "2_2") (pintype "unspecified"))
      (node (ref "C4") (pin "1") (pinfunction "1_1") (pintype "unspecified"))
      (node (ref "C40") (pin "2") (pinfunction "2_2") (pintype "unspecified"))
      (node (ref "C41") (pin "2") (pinfunction "2_2") (pintype "unspecified"))
      (node (ref "C42") (pin "2") (pinfunction "2_2") (pintype "unspecified"))
      (node (ref "C43") (pin "2") (pinfunction "2_2") (pintype "unspecified"))
      (node (ref "C44") (pin "2") (pinfunction "2_2") (pintype "unspecified"))
      (node (ref "C5") (pin "1") (pinfunction "1_1") (pintype "unspecified"))
      (node (ref "C6") (pin "2") (pinfunction "2_2") (pintype "unspecified"))
      (node (ref "C7") (pin "1") (pinfunction "1_1") (pintype "unspecified"))
      (node (ref "C8") (pin "1") (pinfunction "1_1") (pintype "unspecified"))
      (node (ref "C9") (pin "1") (pinfunction "1_1") (pintype "unspecified"))
      (node (ref "CARD1") (pin "10") (pinfunction "10_10") (pintype "unspecified"))
      (node (ref "CARD1") (pin "11") (pinfunction "11_11") (pintype "unspecified"))
      (node (ref "CARD1") (pin "12") (pinfunction "12_12") (pintype "unspecified"))
      (node (ref "CARD1") (pin "13") (pinfunction "13_13") (pintype "unspecified"))
      (node (ref "CARD1") (pin "6") (pinfunction "VSS_6") (pintype "unspecified"))
      (node (ref "LED1") (pin "2") (pinfunction "2_2") (pintype "unspecified"))
      (node (ref "R13") (pin "2") (pinfunction "2_2") (pintype "unspecified"))
      (node (ref "R14") (pin "2") (pinfunction "2_2") (pintype "unspecified"))
      (node (ref "R15") (pin "2") (pinfunction "2_2") (pintype "unspecified"))
      (node (ref "R16") (pin "2") (pinfunction "2_2") (pintype "unspecified"))
      (node (ref "R2") (pin "2") (pinfunction "2_2") (pintype "unspecified"))
      (node (ref "U1") (pin "101") (pinfunction "VSS_101") (pintype "unspecified"))
      (node (ref "U1") (pin "23") (pinfunction "TESTEN_23") (pintype "unspecified"))
      (node (ref "U2") (pin "1") (pinfunction "GND_1") (pintype "passive"))
      (node (ref "U3") (pin "1") (pinfunction "GND_1") (pintype "unspecified"))
      (node (ref "U4") (pin "10") (pinfunction "GND_10") (pintype "unspecified"))
      (node (ref "U5") (pin "10") (pinfunction "GND_10") (pintype "unspecified"))
      (node (ref "U6") (pin "1") (pinfunction "VSS_1") (pintype "unspecified"))
      (node (ref "U6") (pin "14") (pinfunction "VSS_14") (pintype "unspecified"))
      (node (ref "U6") (pin "8") (pinfunction "PMOS_8") (pintype "unspecified"))
      (node (ref "USB1") (pin "25") (pinfunction "EP_25") (pintype "unspecified"))
      (node (ref "USB1") (pin "3") (pinfunction "EP_3") (pintype "unspecified"))
      (node (ref "USB1") (pin "4") (pinfunction "EP_4") (pintype "unspecified"))
      (node (ref "USB1") (pin "A1") (pinfunction "GND_A1") (pintype "unspecified"))
      (node (ref "USB1") (pin "A12") (pinfunction "GND_A12") (pintype "unspecified"))
      (node (ref "USB1") (pin "B1") (pinfunction "GND_B1") (pintype "unspecified"))
      (node (ref "USB1") (pin "B12") (pinfunction "GND_B12") (pintype "unspecified"))
      (node (ref "USB2") (pin "25") (pinfunction "EP_25") (pintype "unspecified"))
      (node (ref "USB2") (pin "3") (pinfunction "EP_3") (pintype "unspecified"))
      (node (ref "USB2") (pin "4") (pinfunction "EP_4") (pintype "unspecified"))
      (node (ref "USB2") (pin "A1") (pinfunction "GND_A1") (pintype "unspecified"))
      (node (ref "USB2") (pin "A12") (pinfunction "GND_A12") (pintype "unspecified"))
      (node (ref "USB2") (pin "B1") (pinfunction "GND_B1") (pintype "unspecified"))
      (node (ref "USB2") (pin "B12") (pinfunction "GND_B12") (pintype "unspecified"))
      (node (ref "USB3") (pin "25") (pinfunction "EP_25") (pintype "unspecified"))
      (node (ref "USB3") (pin "3") (pinfunction "EP_3") (pintype "unspecified"))
      (node (ref "USB3") (pin "4") (pinfunction "EP_4") (pintype "unspecified"))
      (node (ref "USB3") (pin "A1") (pinfunction "GND_A1") (pintype "unspecified"))
      (node (ref "USB3") (pin "A12") (pinfunction "GND_A12") (pintype "unspecified"))
      (node (ref "USB3") (pin "B1") (pinfunction "GND_B1") (pintype "unspecified"))
      (node (ref "USB3") (pin "B12") (pinfunction "GND_B12") (pintype "unspecified"))
      (node (ref "USB4") (pin "11") (pinfunction "EP_11") (pintype "unspecified"))
      (node (ref "USB4") (pin "4") (pinfunction "GND_4") (pintype "unspecified"))
      (node (ref "USB4") (pin "7") (pinfunction "GND_DRAIN_7") (pintype "unspecified"))
      (node (ref "USB5") (pin "4") (pinfunction "GND_4") (pintype "input"))
      (node (ref "USB5") (pin "5") (pinfunction "SH1_5") (pintype "unspecified"))
      (node (ref "USB5") (pin "6") (pinfunction "SH2_6") (pintype "unspecified"))
      (node (ref "X1") (pin "2") (pinfunction "GND_2") (pintype "unspecified"))
      (node (ref "X1") (pin "4") (pinfunction "GND_4") (pintype "unspecified"))
    )
    (net (code "73") (name "Net-(CARD1-CD{slash}DAT3)") (class "Default")
      (node (ref "CARD1") (pin "2") (pinfunction "CD/DAT3_2") (pintype "unspecified"))
      (node (ref "U6") (pin "6") (pinfunction "D3_6") (pintype "unspecified"))
    )
    (net (code "74") (name "Net-(CARD1-CLX)") (class "Default")
      (node (ref "CARD1") (pin "5") (pinfunction "CLX_5") (pintype "unspecified"))
      (node (ref "U6") (pin "4") (pinfunction "CLK_4") (pintype "unspecified"))
    )
    (net (code "75") (name "Net-(CARD1-CMD)") (class "Default")
      (node (ref "CARD1") (pin "3") (pinfunction "CMD_3") (pintype "unspecified"))
      (node (ref "U6") (pin "5") (pinfunction "CMD_5") (pintype "unspecified"))
    )
    (net (code "76") (name "Net-(CARD1-DAT0)") (class "Default")
      (node (ref "CARD1") (pin "7") (pinfunction "DAT0_7") (pintype "unspecified"))
      (node (ref "U6") (pin "3") (pinfunction "D0_3") (pintype "unspecified"))
    )
    (net (code "77") (name "Net-(CARD1-DAT1)") (class "Default")
      (node (ref "CARD1") (pin "8") (pinfunction "DAT1_8") (pintype "unspecified"))
      (node (ref "U6") (pin "2") (pinfunction "D1_2") (pintype "unspecified"))
    )
    (net (code "78") (name "Net-(CARD1-DAT2)") (class "Default")
      (node (ref "CARD1") (pin "1") (pinfunction "DAT2_1") (pintype "unspecified"))
      (node (ref "U6") (pin "7") (pinfunction "D2_7") (pintype "unspecified"))
    )
    (net (code "79") (name "Net-(CARD1-VDD)") (class "Default")
      (node (ref "C13") (pin "2") (pinfunction "2_2") (pintype "unspecified"))
      (node (ref "CARD1") (pin "4") (pinfunction "VDD_4") (pintype "unspecified"))
    )
    (net (code "80") (name "Net-(LED1-Pad1)") (class "Default")
      (node (ref "LED1") (pin "1") (pinfunction "1_1") (pintype "unspecified"))
      (node (ref "R11") (pin "2") (pinfunction "2_2") (pintype "unspecified"))
    )
    (net (code "81") (name "Net-(U1-GPIO12{slash}CFG_STRAP#)") (class "Default")
      (node (ref "R14") (pin "1") (pinfunction "1_1") (pintype "unspecified"))
      (node (ref "U1") (pin "20") (pinfunction "GPIO12/CFG_STRAP#_20") (pintype "unspecified"))
    )
    (net (code "82") (name "Net-(U1-RBIAS)") (class "Default")
      (node (ref "R13") (pin "1") (pinfunction "1_1") (pintype "unspecified"))
      (node (ref "U1") (pin "1") (pinfunction "RBIAS_1") (pintype "unspecified"))
    )
    (net (code "83") (name "Net-(U1-RESET_N)") (class "Default")
      (node (ref "C44") (pin "1") (pinfunction "1_1") (pintype "unspecified"))
      (node (ref "R12") (pin "1") (pinfunction "1_1") (pintype "unspecified"))
      (node (ref "U1") (pin "25") (pinfunction "RESET_N_25") (pintype "unspecified"))
    )
    (net (code "84") (name "Net-(U1-SPI_CE_N{slash}GPIO7{slash}CFG_NON_REM#)") (class "Default")
      (node (ref "R16") (pin "1") (pinfunction "1_1") (pintype "unspecified"))
      (node (ref "U1") (pin "68") (pinfunction "SPI_CE_N/GPIO7/CFG_NON_REM#_68") (pintype "unspecified"))
    )
    (net (code "85") (name "Net-(U1-SPI_DI{slash}GPIO9{slash}CFG_BC_EN#)") (class "Default")
      (node (ref "R15") (pin "1") (pinfunction "1_1") (pintype "unspecified"))
      (node (ref "U1") (pin "67") (pinfunction "SPI_DI/GPIO9/CFG_BC_EN#_67") (pintype "unspecified"))
    )
    (net (code "86") (name "Net-(U1-XTALI{slash}CLKIN)") (class "Default")
      (node (ref "C17") (pin "2") (pinfunction "2_2") (pintype "unspecified"))
      (node (ref "U1") (pin "3") (pinfunction "XTALI/CLKIN_3") (pintype "unspecified"))
    )
    (net (code "87") (name "Net-(U1-XTALO)") (class "Default")
      (node (ref "C16") (pin "2") (pinfunction "2_2") (pintype "unspecified"))
      (node (ref "U1") (pin "4") (pinfunction "XTALO_4") (pintype "unspecified"))
    )
    (net (code "88") (name "Net-(U4-PORT)") (class "Default")
      (node (ref "R3") (pin "1") (pinfunction "1_1") (pintype "unspecified"))
      (node (ref "U4") (pin "4") (pinfunction "PORT_4") (pintype "unspecified"))
    )
    (net (code "89") (name "Net-(U4-VBUS_DET)") (class "Default")
      (node (ref "R5") (pin "2") (pinfunction "2_2") (pintype "unspecified"))
      (node (ref "U4") (pin "5") (pinfunction "VBUS_DET_5") (pintype "unspecified"))
    )
    (net (code "90") (name "Net-(U4-VDD)") (class "Default")
      (node (ref "C10") (pin "1") (pinfunction "1_1") (pintype "unspecified"))
      (node (ref "U4") (pin "12") (pinfunction "VDD_12") (pintype "unspecified"))
    )
    (net (code "91") (name "Net-(U5-PORT)") (class "Default")
      (node (ref "R9") (pin "1") (pinfunction "1_1") (pintype "unspecified"))
      (node (ref "U5") (pin "4") (pinfunction "PORT_4") (pintype "unspecified"))
    )
    (net (code "92") (name "Net-(U5-VBUS_DET)") (class "Default")
      (node (ref "R8") (pin "2") (pinfunction "2_2") (pintype "unspecified"))
      (node (ref "U5") (pin "5") (pinfunction "VBUS_DET_5") (pintype "unspecified"))
    )
    (net (code "93") (name "Net-(U5-VDD)") (class "Default")
      (node (ref "C11") (pin "2") (pinfunction "2_2") (pintype "unspecified"))
      (node (ref "U5") (pin "12") (pinfunction "VDD_12") (pintype "unspecified"))
    )
    (net (code "94") (name "Net-(U6-LED)") (class "Default")
      (node (ref "R11") (pin "1") (pinfunction "1_1") (pintype "unspecified"))
      (node (ref "U6") (pin "12") (pinfunction "LED_12") (pintype "unspecified"))
    )
    (net (code "95") (name "Net-(U6-VDD)") (class "Default")
      (node (ref "C15") (pin "2") (pinfunction "2_2") (pintype "unspecified"))
      (node (ref "U6") (pin "9") (pinfunction "VDD_9") (pintype "unspecified"))
    )
    (net (code "96") (name "Net-(U6-VDDA)") (class "Default")
      (node (ref "C14") (pin "2") (pinfunction "2_2") (pintype "unspecified"))
      (node (ref "U6") (pin "13") (pinfunction "VDDA_13") (pintype "unspecified"))
    )
    (net (code "97") (name "Net-(X1-OSC1)") (class "Default")
      (node (ref "C17") (pin "1") (pinfunction "1_1") (pintype "unspecified"))
      (node (ref "X1") (pin "1") (pinfunction "OSC1_1") (pintype "unspecified"))
    )
    (net (code "98") (name "Net-(X1-OSC2)") (class "Default")
      (node (ref "C16") (pin "1") (pinfunction "1_1") (pintype "unspecified"))
      (node (ref "X1") (pin "3") (pinfunction "OSC2_3") (pintype "unspecified"))
    )
    (net (code "99") (name "unconnected-(CARD1-PadCD)") (class "Default")
      (node (ref "CARD1") (pin "CD") (pinfunction "CD_CD") (pintype "unspecified"))
    )
    (net (code "100") (name "unconnected-(U1-AB2{slash}ATTACHMUX2B{slash}GPIO66-Pad71)") (class "Default")
      (node (ref "U1") (pin "71") (pinfunction "AB2/ATTACHMUX2B/GPIO66_71") (pintype "unspecified+no_connect"))
    )
    (net (code "101") (name "unconnected-(U1-ALT_MUX_EN{slash}GPIO70-Pad63)") (class "Default")
      (node (ref "U1") (pin "63") (pinfunction "ALT_MUX_EN/GPIO70_63") (pintype "unspecified+no_connect"))
    )
    (net (code "102") (name "unconnected-(U1-CC_POL{slash}GPIO71-Pad61)") (class "Default")
      (node (ref "U1") (pin "61") (pinfunction "CC_POL/GPIO71_61") (pintype "unspecified+no_connect"))
    )
    (net (code "103") (name "unconnected-(U1-C_ATTACH2{slash}ATTACHMUX2A{slash}GPIO2-Pad56)") (class "Default")
      (node (ref "U1") (pin "56") (pinfunction "C_ATTACH2/ATTACHMUX2A/GPIO2_56") (pintype "unspecified+no_connect"))
    )
    (net (code "104") (name "unconnected-(U1-GPIO69-Pad69)") (class "Default")
      (node (ref "U1") (pin "69") (pinfunction "GPIO69_69") (pintype "unspecified+no_connect"))
    )
    (net (code "105") (name "unconnected-(U1-HOST_TYPE0{slash}GPIO23-Pad53)") (class "Default")
      (node (ref "U1") (pin "53") (pinfunction "HOST_TYPE0/GPIO23_53") (pintype "unspecified+no_connect"))
    )
    (net (code "106") (name "unconnected-(U1-HOST_TYPE1{slash}GPIO67-Pad55)") (class "Default")
      (node (ref "U1") (pin "55") (pinfunction "HOST_TYPE1/GPIO67_55") (pintype "unspecified+no_connect"))
    )
    (net (code "107") (name "unconnected-(U1-NC-Pad21)") (class "Default")
      (node (ref "U1") (pin "21") (pinfunction "NC_21") (pintype "unspecified+no_connect"))
    )
    (net (code "108") (name "unconnected-(U1-NC-Pad22)") (class "Default")
      (node (ref "U1") (pin "22") (pinfunction "NC_22") (pintype "unspecified+no_connect"))
    )
    (net (code "109") (name "unconnected-(U1-NC-Pad79)") (class "Default")
      (node (ref "U1") (pin "79") (pinfunction "NC_79") (pintype "unspecified+no_connect"))
    )
    (net (code "110") (name "unconnected-(U1-NC-Pad80)") (class "Default")
      (node (ref "U1") (pin "80") (pinfunction "NC_80") (pintype "unspecified+no_connect"))
    )
    (net (code "111") (name "unconnected-(U1-PRT_CTL1{slash}GPIO17-Pad70)") (class "Default")
      (node (ref "U1") (pin "70") (pinfunction "PRT_CTL1/GPIO17_70") (pintype "unspecified"))
    )
    (net (code "112") (name "unconnected-(U1-PRT_CTL2{slash}GPIO19-Pad58)") (class "Default")
      (node (ref "U1") (pin "58") (pinfunction "PRT_CTL2/GPIO19_58") (pintype "unspecified"))
    )
    (net (code "113") (name "unconnected-(U1-PRT_CTL3{slash}GPIO21-Pad52)") (class "Default")
      (node (ref "U1") (pin "52") (pinfunction "PRT_CTL3/GPIO21_52") (pintype "unspecified"))
    )
    (net (code "114") (name "unconnected-(U1-PRT_CTL4{slash}GPIO22-Pad51)") (class "Default")
      (node (ref "U1") (pin "51") (pinfunction "PRT_CTL4/GPIO22_51") (pintype "unspecified"))
    )
    (net (code "115") (name "unconnected-(U1-PRT_CTL5{slash}GPIO18-Pad62)") (class "Default")
      (node (ref "U1") (pin "62") (pinfunction "PRT_CTL5/GPIO18_62") (pintype "unspecified"))
    )
    (net (code "116") (name "unconnected-(U1-PRT_CTL6{slash}GANG_PWR{slash}GPIO20-Pad57)") (class "Default")
      (node (ref "U1") (pin "57") (pinfunction "PRT_CTL6/GANG_PWR/GPIO20_57") (pintype "unspecified"))
    )
    (net (code "117") (name "unconnected-(U1-SMBCLK{slash}GPIO8-Pad75)") (class "Default")
      (node (ref "U1") (pin "75") (pinfunction "SMBCLK/GPIO8_75") (pintype "unspecified+no_connect"))
    )
    (net (code "118") (name "unconnected-(U1-SMBDATA{slash}GPIO6-Pad74)") (class "Default")
      (node (ref "U1") (pin "74") (pinfunction "SMBDATA/GPIO6_74") (pintype "unspecified+no_connect"))
    )
    (net (code "119") (name "unconnected-(U1-SPI_CLK{slash}GPIO4-Pad65)") (class "Default")
      (node (ref "U1") (pin "65") (pinfunction "SPI_CLK/GPIO4_65") (pintype "unspecified+no_connect"))
    )
    (net (code "120") (name "unconnected-(U1-SPI_DO{slash}GPIO5-Pad66)") (class "Default")
      (node (ref "U1") (pin "66") (pinfunction "SPI_DO/GPIO5_66") (pintype "unspecified+no_connect"))
    )
    (net (code "121") (name "unconnected-(U1-SUSP_IND{slash}GPIO68-Pad77)") (class "Default")
      (node (ref "U1") (pin "77") (pinfunction "SUSP_IND/GPIO68_77") (pintype "unspecified+no_connect"))
    )
    (net (code "122") (name "unconnected-(U2-VOUT-Pad4)") (class "Default")
      (node (ref "U2") (pin "4") (pinfunction "VOUT_4") (pintype "passive"))
    )
    (net (code "123") (name "unconnected-(U4-CURRENT_MODE-Pad3)") (class "Default")
      (node (ref "U4") (pin "3") (pinfunction "CURRENT_MODE_3") (pintype "unspecified+no_connect"))
    )
    (net (code "124") (name "unconnected-(U4-OUT1-Pad7)") (class "Default")
      (node (ref "U4") (pin "7") (pinfunction "OUT1_7") (pintype "unspecified+no_connect"))
    )
    (net (code "125") (name "unconnected-(U4-OUT2-Pad8)") (class "Default")
      (node (ref "U4") (pin "8") (pinfunction "OUT2_8") (pintype "unspecified+no_connect"))
    )
    (net (code "126") (name "unconnected-(U4-VCONN_FAULT-Pad6)") (class "Default")
      (node (ref "U4") (pin "6") (pinfunction "VCONN_FAULT_6") (pintype "unspecified+no_connect"))
    )
    (net (code "127") (name "unconnected-(U5-CURRENT_MODE-Pad3)") (class "Default")
      (node (ref "U5") (pin "3") (pinfunction "CURRENT_MODE_3") (pintype "unspecified+no_connect"))
    )
    (net (code "128") (name "unconnected-(U5-OUT1-Pad7)") (class "Default")
      (node (ref "U5") (pin "7") (pinfunction "OUT1_7") (pintype "unspecified+no_connect"))
    )
    (net (code "129") (name "unconnected-(U5-OUT2-Pad8)") (class "Default")
      (node (ref "U5") (pin "8") (pinfunction "OUT2_8") (pintype "unspecified+no_connect"))
    )
    (net (code "130") (name "unconnected-(U5-VCONN_FAULT-Pad6)") (class "Default")
      (node (ref "U5") (pin "6") (pinfunction "VCONN_FAULT_6") (pintype "unspecified+no_connect"))
    )
    (net (code "131") (name "unconnected-(U6-GPIO-Pad11)") (class "Default")
      (node (ref "U6") (pin "11") (pinfunction "GPIO_11") (pintype "unspecified+no_connect"))
    )
    (net (code "132") (name "unconnected-(USB4-EP-Pad10)") (class "Default")
      (node (ref "USB4") (pin "10") (pinfunction "EP_10") (pintype "unspecified"))
    )
  )
)
